# attinier84-motherboard-mk-1_1.net
KiCad netlist of a schematic drawn in EAGLE
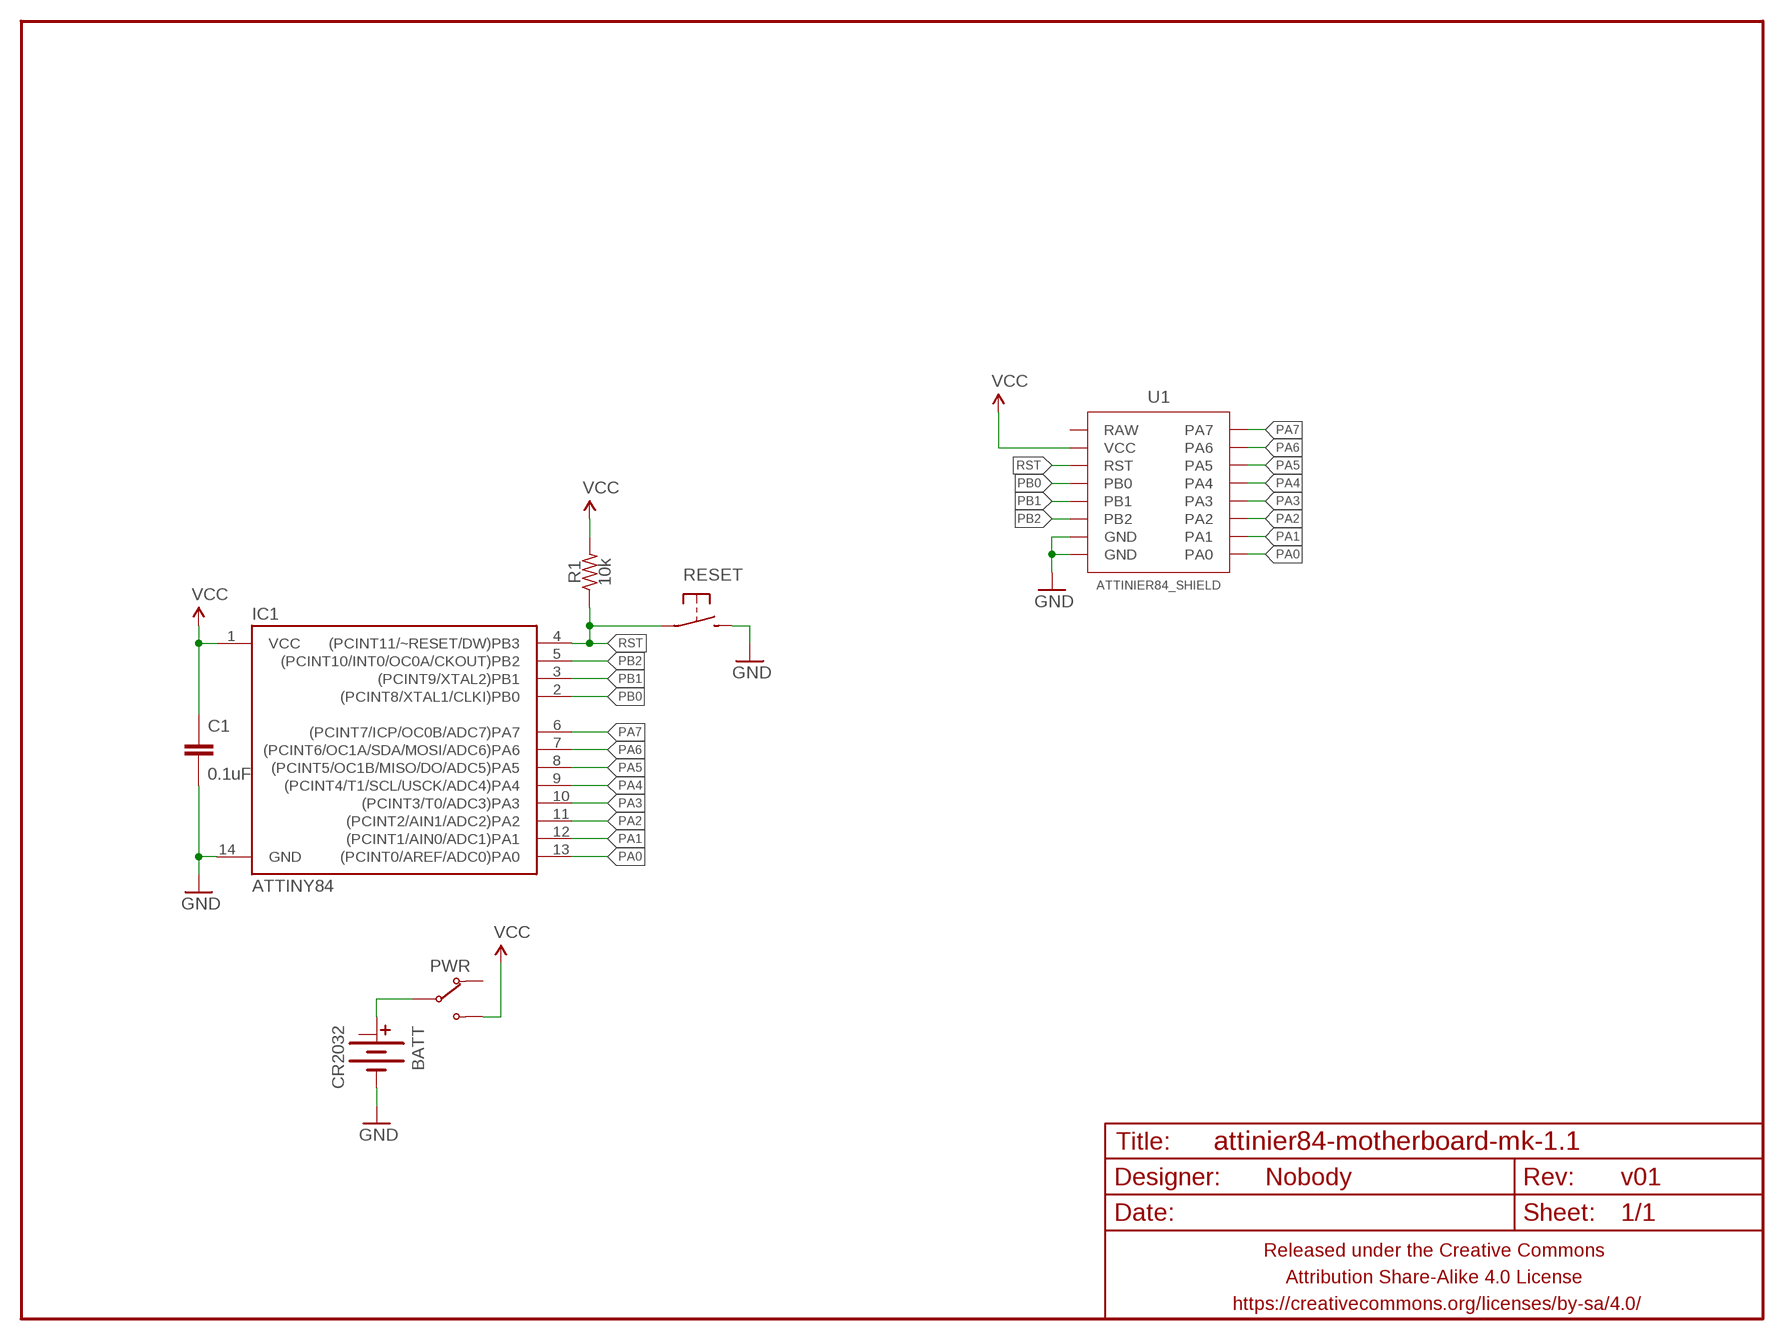
[diagram p0: schematic, sheet 1]

(export (version "E")
  (design (tool "Eeschema 10.0.6"))
  (components
    (comp (ref "BATT")
      (value "CR2032")
      (footprint "eagle-import:BATTCON_20MM_MINE")
      (libsource (lib "eagle-import") (part "BATTERY-COINCR2032_SMD"))
    )
    (comp (ref "C1")
      (value "0.1uF")
      (footprint "eagle-import:C0805")
      (libsource (lib "eagle-import") (part "CAPACITOR-CERAMICC0805"))
    )
    (comp (ref "FRAME1")
      (value "FRAME-LETTERNO_PACKAGE")
      (footprint "eagle-import:DUMMY")
      (fields (field (name "DESIGNER") "Nobody"))
      (libsource (lib "eagle-import") (part "FRAME-LETTERNO_PACKAGE"))
    )
    (comp (ref "IC1")
      (value "ATTINY84")
      (footprint "eagle-import:SO14")
      (libsource (lib "eagle-import") (part "ATTINY84"))
    )
    (comp (ref "PWR")
      (value "SWITCH-SPDTSMD-RA")
      (footprint "eagle-import:SWITCH-SPDT-SMD-RA")
      (libsource (lib "eagle-import") (part "SWITCH-SPDTSMD-RA"))
    )
    (comp (ref "R1")
      (value "10k")
      (footprint "eagle-import:R0805")
      (libsource (lib "eagle-import") (part "RESISTORR0805"))
    )
    (comp (ref "RESET")
      (value "SPST-NO-TACT6MM-SMD")
      (footprint "eagle-import:DTSM-6")
      (libsource (lib "eagle-import") (part "SPST-NO-TACT6MM-SMD"))
    )
    (comp (ref "U1")
      (value "ATTINIER84_SHIELD")
      (footprint "eagle-import:ATTINIER84_SHIELD")
      (libsource (lib "eagle-import") (part "ATTINIER84_SHIELD"))
    )
  )
  (nets
    (net (code "1") (name "GND") (class "Default")
      (node (ref "BATT") (pin "BOTTOM") (pinfunction "-_BOTTOM") (pintype "bidirectional"))
      (node (ref "C1") (pin "2") (pinfunction "2_2") (pintype "passive"))
      (node (ref "IC1") (pin "14") (pinfunction "GND_14") (pintype "bidirectional"))
      (node (ref "RESET") (pin "3") (pinfunction "2_3") (pintype "passive"))
      (node (ref "RESET") (pin "4") (pinfunction "2_4") (pintype "passive"))
      (node (ref "U1") (pin "GND@1") (pinfunction "GND_GND@1") (pintype "bidirectional"))
      (node (ref "U1") (pin "GND@2") (pinfunction "GND_GND@2") (pintype "bidirectional"))
    )
    (net (code "2") (name "Net-(BATT-+)") (class "Default")
      (node (ref "BATT") (pin "TOP@1") (pinfunction "+_TOP@1") (pintype "bidirectional"))
      (node (ref "PWR") (pin "2") (pinfunction "COM_2") (pintype "passive"))
    )
    (net (code "3") (name "PA0") (class "Default")
      (node (ref "IC1") (pin "13") (pinfunction "(PCINT0/AREF/ADC0)PA0_13") (pintype "bidirectional"))
      (node (ref "U1") (pin "PA0") (pinfunction "PA0_PA0") (pintype "bidirectional"))
    )
    (net (code "4") (name "PA1") (class "Default")
      (node (ref "IC1") (pin "12") (pinfunction "(PCINT1/AIN0/ADC1)PA1_12") (pintype "bidirectional"))
      (node (ref "U1") (pin "PA1") (pinfunction "PA1_PA1") (pintype "bidirectional"))
    )
    (net (code "5") (name "PA2") (class "Default")
      (node (ref "IC1") (pin "11") (pinfunction "(PCINT2/AIN1/ADC2)PA2_11") (pintype "bidirectional"))
      (node (ref "U1") (pin "PA2") (pinfunction "PA2_PA2") (pintype "bidirectional"))
    )
    (net (code "6") (name "PA3") (class "Default")
      (node (ref "IC1") (pin "10") (pinfunction "(PCINT3/T0/ADC3)PA3_10") (pintype "bidirectional"))
      (node (ref "U1") (pin "PA3") (pinfunction "PA3_PA3") (pintype "bidirectional"))
    )
    (net (code "7") (name "PA4") (class "Default")
      (node (ref "IC1") (pin "9") (pinfunction "(PCINT4/T1/SCL/USCK/ADC4)PA4_9") (pintype "bidirectional"))
      (node (ref "U1") (pin "PA4") (pinfunction "PA4_PA4") (pintype "bidirectional"))
    )
    (net (code "8") (name "PA5") (class "Default")
      (node (ref "IC1") (pin "8") (pinfunction "(PCINT5/OC1B/MISO/DO/ADC5)PA5_8") (pintype "bidirectional"))
      (node (ref "U1") (pin "PA5") (pinfunction "PA5_PA5") (pintype "bidirectional"))
    )
    (net (code "9") (name "PA6") (class "Default")
      (node (ref "IC1") (pin "7") (pinfunction "(PCINT6/OC1A/SDA/MOSI/ADC6)PA6_7") (pintype "bidirectional"))
      (node (ref "U1") (pin "PA6") (pinfunction "PA6_PA6") (pintype "bidirectional"))
    )
    (net (code "10") (name "PA7") (class "Default")
      (node (ref "IC1") (pin "6") (pinfunction "(PCINT7/ICP/OC0B/ADC7)PA7_6") (pintype "bidirectional"))
      (node (ref "U1") (pin "PA7") (pinfunction "PA7_PA7") (pintype "bidirectional"))
    )
    (net (code "11") (name "PB0") (class "Default")
      (node (ref "IC1") (pin "2") (pinfunction "(PCINT8/XTAL1/CLKI)PB0_2") (pintype "bidirectional"))
      (node (ref "U1") (pin "PB0") (pinfunction "PB0_PB0") (pintype "bidirectional"))
    )
    (net (code "12") (name "PB1") (class "Default")
      (node (ref "IC1") (pin "3") (pinfunction "(PCINT9/XTAL2)PB1_3") (pintype "bidirectional"))
      (node (ref "U1") (pin "PB1") (pinfunction "PB1_PB1") (pintype "bidirectional"))
    )
    (net (code "13") (name "PB2") (class "Default")
      (node (ref "IC1") (pin "5") (pinfunction "(PCINT10/INT0/OC0A/CKOUT)PB2_5") (pintype "bidirectional"))
      (node (ref "U1") (pin "PB2") (pinfunction "PB2_PB2") (pintype "bidirectional"))
    )
    (net (code "14") (name "RST") (class "Default")
      (node (ref "IC1") (pin "4") (pinfunction "(PCINT11/~{RESET/DW})PB3_4") (pintype "bidirectional"))
      (node (ref "R1") (pin "1") (pinfunction "1_1") (pintype "passive"))
      (node (ref "RESET") (pin "1") (pinfunction "1_1") (pintype "passive"))
      (node (ref "RESET") (pin "2") (pinfunction "1_2") (pintype "passive"))
      (node (ref "U1") (pin "RST") (pinfunction "RST_RST") (pintype "bidirectional"))
    )
    (net (code "15") (name "VCC") (class "Default")
      (node (ref "C1") (pin "1") (pinfunction "1_1") (pintype "passive"))
      (node (ref "IC1") (pin "1") (pinfunction "VCC_1") (pintype "bidirectional"))
      (node (ref "PWR") (pin "1") (pinfunction "NO_1") (pintype "passive"))
      (node (ref "R1") (pin "2") (pinfunction "2_2") (pintype "passive"))
      (node (ref "U1") (pin "VCC") (pinfunction "VCC_VCC") (pintype "bidirectional"))
    )
    (net (code "16") (name "unconnected-(BATT-+1-PadTOP@2)") (class "Default")
      (node (ref "BATT") (pin "TOP@2") (pinfunction "+1_TOP@2") (pintype "bidirectional"))
    )
    (net (code "17") (name "unconnected-(PWR-NC-Pad3)") (class "Default")
      (node (ref "PWR") (pin "3") (pinfunction "NC_3") (pintype "passive"))
    )
    (net (code "18") (name "unconnected-(U1-PadRAW)") (class "Default")
      (node (ref "U1") (pin "RAW") (pinfunction "RAW_RAW") (pintype "bidirectional"))
    )
  )
)
